# DanielKnapp-smd.net
KiCad netlist of a schematic drawn in EAGLE
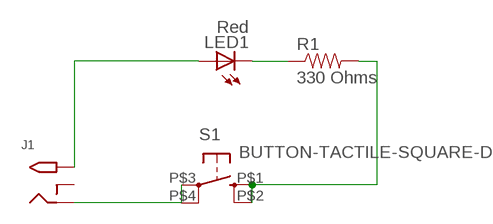
[diagram p0: schematic, sheet 1]

(export (version "E")
  (design (tool "Eeschema 10.0.6"))
  (components
    (comp (ref "J1")
      (value "2.1MMJACKTHM")
      (footprint "eagle-import:PJ-102A")
      (libsource (lib "eagle-import") (part "2.1MMJACKTHM"))
    )
    (comp (ref "LED1")
      (value "Red")
      (footprint "eagle-import:LED5MM")
      (libsource (lib "eagle-import") (part "LED5MM"))
    )
    (comp (ref "R1")
      (value "330 Ohms")
      (footprint "eagle-import:AXIAL-0.3")
      (libsource (lib "eagle-import") (part "RESISTORAXIAL-0.3"))
    )
    (comp (ref "S1")
      (value "BUTTON-TACTILE-SQUARE-DK")
      (footprint "eagle-import:BUTTON-TACTILE-SQUARE-DK")
      (libsource (lib "eagle-import") (part "BUTTON-TACTILE-SQUARE-DK"))
    )
  )
  (nets
    (net (code "1") (name "Net-(J1-PadTIP)") (class "Default")
      (node (ref "J1") (pin "TIP") (pinfunction "TIP_TIP") (pintype "bidirectional"))
      (node (ref "LED1") (pin "A") (pinfunction "A_A") (pintype "passive"))
    )
    (net (code "2") (name "Net-(LED1-C)") (class "Default")
      (node (ref "LED1") (pin "K") (pinfunction "C_K") (pintype "passive"))
      (node (ref "R1") (pin "P$1") (pinfunction "1_P$1") (pintype "passive"))
    )
    (net (code "3") (name "Net-(R1-2)") (class "Default")
      (node (ref "R1") (pin "P$2") (pinfunction "2_P$2") (pintype "passive"))
      (node (ref "S1") (pin "P$1") (pinfunction "S_P$1") (pintype "passive"))
      (node (ref "S1") (pin "P$2") (pinfunction "S1_P$2") (pintype "passive"))
    )
    (net (code "4") (name "Net-(S1-P)") (class "Default")
      (node (ref "J1") (pin "RING") (pinfunction "RING_RING") (pintype "bidirectional"))
      (node (ref "S1") (pin "P$3") (pinfunction "P_P$3") (pintype "passive"))
      (node (ref "S1") (pin "P$4") (pinfunction "P1_P$4") (pintype "passive"))
    )
    (net (code "5") (name "unconnected-(J1-PadRING_SW)") (class "Default")
      (node (ref "J1") (pin "RING_SW") (pinfunction "RING_SW_RING_SW") (pintype "bidirectional"))
    )
  )
)
